# DDR3.net
KiCad netlist of a schematic drawn in Altium Designer
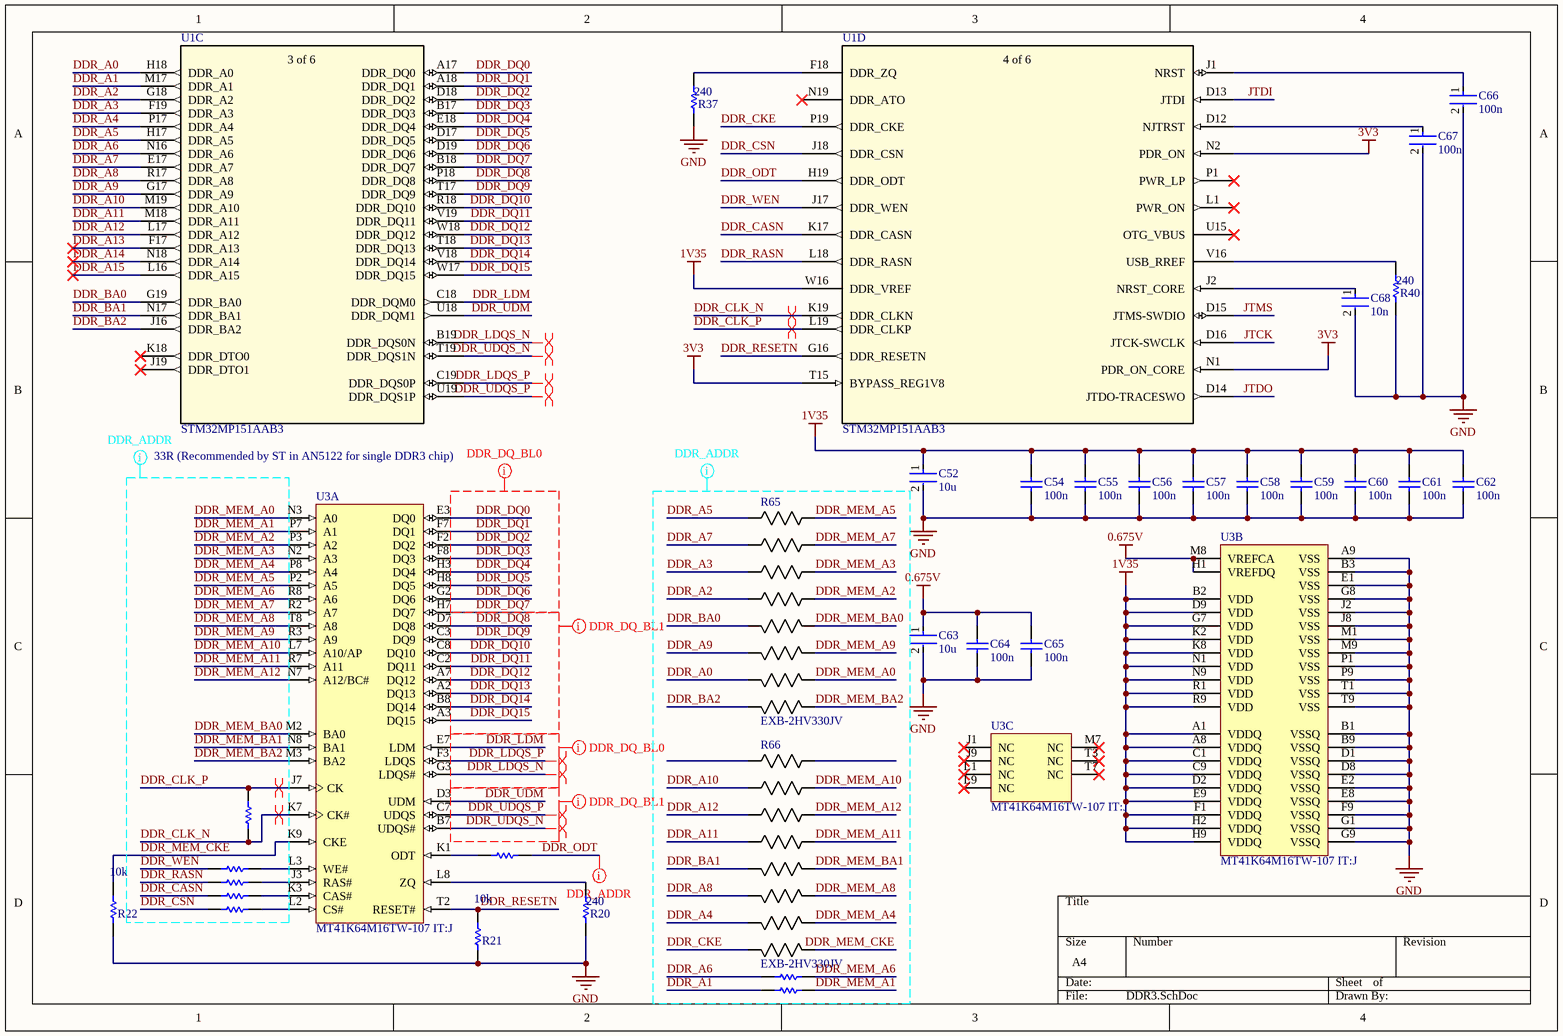
[diagram p0: DDR3.SchDoc]

(export (version "E")
  (design (tool "Eeschema 10.0.6"))
  (components
    (comp (ref "C52")
      (value "10u")
      (footprint "FP-CC0805-0_85-MFG")
      (description "CAP CER 0.1UF 50V X7R 0805")
      (fields (field (name "TOLERANCE") "0.1") (field (name "MANUFACTURER PART NUMBER") "CC0805KRX7R9BB104"))
      (libsource (lib "Altium Content Vault") (part "11868f565c42a9108669ba33697ecf6"))
    )
    (comp (ref "C54")
      (value "100n")
      (footprint "CAPC0603X33X15LL03T05")
      (fields
        (field (name "PART NUMBER") "02016D104KAT2A")
        (field (name "MANUFACTURER") "AVX Interconnect / Elco")
      )
      (libsource (lib "Altium Content Vault") (part "CAP"))
    )
    (comp (ref "C55")
      (value "100n")
      (footprint "CAPC0603X33X15LL03T05")
      (fields
        (field (name "PART NUMBER") "02016D104KAT2A")
        (field (name "MANUFACTURER") "AVX Interconnect / Elco")
      )
      (libsource (lib "Altium Content Vault") (part "CAP"))
    )
    (comp (ref "C56")
      (value "100n")
      (footprint "CAPC0603X33X15LL03T05")
      (fields
        (field (name "PART NUMBER") "02016D104KAT2A")
        (field (name "MANUFACTURER") "AVX Interconnect / Elco")
      )
      (libsource (lib "Altium Content Vault") (part "CAP"))
    )
    (comp (ref "C57")
      (value "100n")
      (footprint "CAPC0603X33X15LL03T05")
      (fields
        (field (name "PART NUMBER") "02016D104KAT2A")
        (field (name "MANUFACTURER") "AVX Interconnect / Elco")
      )
      (libsource (lib "Altium Content Vault") (part "CAP"))
    )
    (comp (ref "C58")
      (value "100n")
      (footprint "CAPC0603X33X15LL03T05")
      (fields
        (field (name "PART NUMBER") "02016D104KAT2A")
        (field (name "MANUFACTURER") "AVX Interconnect / Elco")
      )
      (libsource (lib "Altium Content Vault") (part "CAP"))
    )
    (comp (ref "C59")
      (value "100n")
      (footprint "CAPC0603X33X15LL03T05")
      (fields
        (field (name "PART NUMBER") "02016D104KAT2A")
        (field (name "MANUFACTURER") "AVX Interconnect / Elco")
      )
      (libsource (lib "Altium Content Vault") (part "CAP"))
    )
    (comp (ref "C60")
      (value "100n")
      (footprint "CAPC0603X33X15LL03T05")
      (fields
        (field (name "PART NUMBER") "02016D104KAT2A")
        (field (name "MANUFACTURER") "AVX Interconnect / Elco")
      )
      (libsource (lib "Altium Content Vault") (part "CAP"))
    )
    (comp (ref "C61")
      (value "100n")
      (footprint "CAPC0603X33X15LL03T05")
      (fields
        (field (name "PART NUMBER") "02016D104KAT2A")
        (field (name "MANUFACTURER") "AVX Interconnect / Elco")
      )
      (libsource (lib "Altium Content Vault") (part "CAP"))
    )
    (comp (ref "C62")
      (value "100n")
      (footprint "CAPC0603X33X15LL03T05")
      (fields
        (field (name "PART NUMBER") "02016D104KAT2A")
        (field (name "MANUFACTURER") "AVX Interconnect / Elco")
      )
      (libsource (lib "Altium Content Vault") (part "CAP"))
    )
    (comp (ref "C63")
      (value "10u")
      (footprint "FP-CC0805-0_85-MFG")
      (description "CAP CER 0.1UF 50V X7R 0805")
      (fields (field (name "TOLERANCE") "0.1") (field (name "MANUFACTURER PART NUMBER") "CC0805KRX7R9BB104"))
      (libsource (lib "Altium Content Vault") (part "11868f565c42a9108669ba33697ecf6"))
    )
    (comp (ref "C64")
      (value "100n")
      (footprint "CAPC0603X33X15LL03T05")
      (fields
        (field (name "PART NUMBER") "02016D104KAT2A")
        (field (name "MANUFACTURER") "AVX Interconnect / Elco")
      )
      (libsource (lib "Altium Content Vault") (part "CAP"))
    )
    (comp (ref "C65")
      (value "100n")
      (footprint "CAPC0603X33X15LL03T05")
      (fields
        (field (name "PART NUMBER") "02016D104KAT2A")
        (field (name "MANUFACTURER") "AVX Interconnect / Elco")
      )
      (libsource (lib "Altium Content Vault") (part "CAP"))
    )
    (comp (ref "C66")
      (value "100n")
      (footprint "FP-C0603C-CF-MFG")
      (description "CAP CER 0.1UF 50V X7R 0603")
      (fields (field (name "TOLERANCE") "0.1") (field (name "MANUFACTURER") "KEMET"))
      (libsource (lib "Altium Content Vault") (part "b4654b650e69147ec39a6b967a45e02"))
    )
    (comp (ref "C67")
      (value "100n")
      (footprint "FP-C0603C-CF-MFG")
      (description "CAP CER 0.1UF 50V X7R 0603")
      (fields (field (name "TOLERANCE") "0.1") (field (name "MANUFACTURER") "KEMET"))
      (libsource (lib "Altium Content Vault") (part "b4654b650e69147ec39a6b967a45e02"))
    )
    (comp (ref "C68")
      (value "10n")
      (footprint "FP-C0603C-CF-MFG")
      (description "CAP CER 0.1UF 50V X7R 0603")
      (fields (field (name "TOLERANCE") "0.1") (field (name "MANUFACTURER") "KEMET"))
      (libsource (lib "Altium Content Vault") (part "b4654b650e69147ec39a6b967a45e02"))
    )
    (comp (ref "R13")
      (value "CRCW0201100RFKED")
      (footprint "RESC0603X28X15ML05T05")
      (fields (field (name "MANUFACTURER") "Vishay"))
      (libsource (lib "Altium Content Vault") (part "RES"))
    )
    (comp (ref "R14")
      (value "CRCW0201100RFKED")
      (footprint "RESC0603X28X15ML05T05")
      (fields (field (name "MANUFACTURER") "Vishay"))
      (libsource (lib "Altium Content Vault") (part "RES"))
    )
    (comp (ref "R15")
      (value "CRCW0201100RFKED")
      (footprint "RESC0603X28X15ML05T05")
      (fields (field (name "MANUFACTURER") "Vishay"))
      (libsource (lib "Altium Content Vault") (part "RES"))
    )
    (comp (ref "R16")
      (value "CRCW0201100RFKED")
      (footprint "RESC0603X28X15ML05T05")
      (fields (field (name "MANUFACTURER") "Vishay"))
      (libsource (lib "Altium Content Vault") (part "RES"))
    )
    (comp (ref "R17")
      (value "CRCW0201100RFKED")
      (footprint "RESC0603X28X15ML05T05")
      (fields (field (name "MANUFACTURER") "Vishay"))
      (libsource (lib "Altium Content Vault") (part "RES"))
    )
    (comp (ref "R18")
      (value "CRCW0201100RFKED")
      (footprint "RESC0603X28X15ML05T05")
      (fields (field (name "MANUFACTURER") "Vishay"))
      (libsource (lib "Altium Content Vault") (part "RES"))
    )
    (comp (ref "R19")
      (value "CRCW0201100RFKED")
      (footprint "RESC0603X28X15ML05T05")
      (fields (field (name "MANUFACTURER") "Vishay"))
      (libsource (lib "Altium Content Vault") (part "RES"))
    )
    (comp (ref "R20")
      (value "240")
      (footprint "RESC1609X50X30NL8T20")
      (description "Chip Resistor, 10 KOhm, +/- 1%, 100 mW, -55 to 155 degC, 0603 (1608 Metric), RoHS, Tape and Reel")
      (fields (field (name "MANUFACTURER") "Vishay Semiconductor"))
      (libsource (lib "Altium Content Vault") (part "RES-2"))
    )
    (comp (ref "R21")
      (value "10k")
      (footprint "RESC0603X28X15ML05T05")
      (fields (field (name "PART NUMBER") "CRCW0201100RFKED") (field (name "MANUFACTURER") "Vishay"))
      (libsource (lib "Altium Content Vault") (part "RES"))
    )
    (comp (ref "R22")
      (value "10k")
      (footprint "RESC0603X28X15ML05T05")
      (fields (field (name "PART NUMBER") "CRCW0201100RFKED") (field (name "MANUFACTURER") "Vishay"))
      (libsource (lib "Altium Content Vault") (part "RES"))
    )
    (comp (ref "R29")
      (value "CRCW0201100RFKED")
      (footprint "RESC0603X28X15ML05T05")
      (fields (field (name "MANUFACTURER") "Vishay"))
      (libsource (lib "Altium Content Vault") (part "RES"))
    )
    (comp (ref "R37")
      (value "240")
      (footprint "RESC1609X50X30NL8T20")
      (description "Chip Resistor, 10 KOhm, +/- 1%, 100 mW, -55 to 155 degC, 0603 (1608 Metric), RoHS, Tape and Reel")
      (fields (field (name "MANUFACTURER") "Vishay Semiconductor"))
      (libsource (lib "Altium Content Vault") (part "RES-2"))
    )
    (comp (ref "R40")
      (value "240")
      (footprint "RESC1609X50X30NL8T20")
      (description "Chip Resistor, 10 KOhm, +/- 1%, 100 mW, -55 to 155 degC, 0603 (1608 Metric), RoHS, Tape and Reel")
      (fields (field (name "MANUFACTURER") "Vishay Semiconductor"))
      (libsource (lib "Altium Content Vault") (part "RES-2"))
    )
    (comp (ref "R65")
      (value "EXB-2HV330JV")
      (footprint "RES_EXB2HV")
      (description "No Description Available")
      (libsource (lib "Master") (part "EXB-2HV330JV"))
    )
    (comp (ref "R66")
      (value "EXB-2HV330JV")
      (footprint "RES_EXB2HV")
      (description "No Description Available")
      (libsource (lib "Master") (part "EXB-2HV330JV"))
    )
    (comp (ref "U1")
      (value "STM32MP151AAB3")
      (footprint "LFBGA354_16X16_STM")
      (description "No Description Available")
      (libsource (lib "Master") (part "STM32MP151AAB3"))
    )
    (comp (ref "U3")
      (value "MT41K64M16TW-107 IT:J")
      (footprint "MICT-TW-96")
      (description "1 Gb DDR3L 1866 SDRAM, 64 Mb x 16, 1.07 ns, 1.35 V, -40 to 95 degC, 96-Ball FBGA (TW), RoHS, Tray")
      (fields (field (name "MANUFACTURER") "Micron"))
      (libsource (lib "Altium Content Vault") (part "MICT-MT41K_1G-FBGA96"))
    )
  )
  (nets
    (net (code "1") (name "/DDR_A0") (class "Default")
      (node (ref "R65") (pin "7") (pinfunction "7_7") (pintype "passive"))
      (node (ref "U1") (pin "H18") (pinfunction "DDR_A0_H18") (pintype "output"))
    )
    (net (code "2") (name "/DDR_A1") (class "Default")
      (node (ref "R19") (pin "1") (pinfunction "1_1") (pintype "passive"))
      (node (ref "U1") (pin "M17") (pinfunction "DDR_A1_M17") (pintype "output"))
    )
    (net (code "3") (name "/DDR_A2") (class "Default")
      (node (ref "R65") (pin "4") (pinfunction "4_4") (pintype "passive"))
      (node (ref "U1") (pin "G18") (pinfunction "DDR_A2_G18") (pintype "output"))
    )
    (net (code "4") (name "/DDR_A3") (class "Default")
      (node (ref "R65") (pin "3") (pinfunction "3_3") (pintype "passive"))
      (node (ref "U1") (pin "F19") (pinfunction "DDR_A3_F19") (pintype "output"))
    )
    (net (code "5") (name "/DDR_A4") (class "Default")
      (node (ref "R66") (pin "7") (pinfunction "7_7") (pintype "passive"))
      (node (ref "U1") (pin "P17") (pinfunction "DDR_A4_P17") (pintype "output"))
    )
    (net (code "6") (name "/DDR_A5") (class "Default")
      (node (ref "R65") (pin "1") (pinfunction "1_1") (pintype "passive"))
      (node (ref "U1") (pin "H17") (pinfunction "DDR_A5_H17") (pintype "output"))
    )
    (net (code "7") (name "/DDR_A6") (class "Default")
      (node (ref "R18") (pin "1") (pinfunction "1_1") (pintype "passive"))
      (node (ref "U1") (pin "N16") (pinfunction "DDR_A6_N16") (pintype "output"))
    )
    (net (code "8") (name "/DDR_A7") (class "Default")
      (node (ref "R65") (pin "2") (pinfunction "2_2") (pintype "passive"))
      (node (ref "U1") (pin "E17") (pinfunction "DDR_A7_E17") (pintype "output"))
    )
    (net (code "9") (name "/DDR_A8") (class "Default")
      (node (ref "R66") (pin "6") (pinfunction "6_6") (pintype "passive"))
      (node (ref "U1") (pin "R17") (pinfunction "DDR_A8_R17") (pintype "output"))
    )
    (net (code "10") (name "/DDR_A9") (class "Default")
      (node (ref "R65") (pin "6") (pinfunction "6_6") (pintype "passive"))
      (node (ref "U1") (pin "G17") (pinfunction "DDR_A9_G17") (pintype "output"))
    )
    (net (code "11") (name "/DDR_A10") (class "Default")
      (node (ref "R66") (pin "2") (pinfunction "2_2") (pintype "passive"))
      (node (ref "U1") (pin "M19") (pinfunction "DDR_A10_M19") (pintype "output"))
    )
    (net (code "12") (name "/DDR_A11") (class "Default")
      (node (ref "R66") (pin "4") (pinfunction "4_4") (pintype "passive"))
      (node (ref "U1") (pin "M18") (pinfunction "DDR_A11_M18") (pintype "output"))
    )
    (net (code "13") (name "/DDR_A12") (class "Default")
      (node (ref "R66") (pin "3") (pinfunction "3_3") (pintype "passive"))
      (node (ref "U1") (pin "L17") (pinfunction "DDR_A12_L17") (pintype "output"))
    )
    (net (code "14") (name "/DDR_A13") (class "Default")
      (node (ref "U1") (pin "F17") (pinfunction "DDR_A13_F17") (pintype "output+no_connect"))
    )
    (net (code "15") (name "/DDR_A14") (class "Default")
      (node (ref "U1") (pin "N18") (pinfunction "DDR_A14_N18") (pintype "output+no_connect"))
    )
    (net (code "16") (name "/DDR_A15") (class "Default")
      (node (ref "U1") (pin "L16") (pinfunction "DDR_A15_L16") (pintype "output+no_connect"))
    )
    (net (code "17") (name "/DDR_BA0") (class "Default")
      (node (ref "R65") (pin "5") (pinfunction "5_5") (pintype "passive"))
      (node (ref "U1") (pin "G19") (pinfunction "DDR_BA0_G19") (pintype "output"))
    )
    (net (code "18") (name "/DDR_BA1") (class "Default")
      (node (ref "R66") (pin "5") (pinfunction "5_5") (pintype "passive"))
      (node (ref "U1") (pin "N17") (pinfunction "DDR_BA1_N17") (pintype "output"))
    )
    (net (code "19") (name "/DDR_BA2") (class "Default")
      (node (ref "R65") (pin "8") (pinfunction "8_8") (pintype "passive"))
      (node (ref "U1") (pin "J16") (pinfunction "DDR_BA2_J16") (pintype "output"))
    )
    (net (code "20") (name "/DDR_CASN") (class "Default")
      (node (ref "R16") (pin "1") (pinfunction "1_1") (pintype "passive"))
      (node (ref "U1") (pin "K17") (pinfunction "DDR_CASN_K17") (pintype "output"))
    )
    (net (code "21") (name "/DDR_CKE") (class "Default")
      (node (ref "R66") (pin "8") (pinfunction "8_8") (pintype "passive"))
      (node (ref "U1") (pin "P19") (pinfunction "DDR_CKE_P19") (pintype "output"))
    )
    (net (code "22") (name "/DDR_CLK_N") (class "Default")
      (node (ref "R29") (pin "1") (pinfunction "1_1") (pintype "passive"))
      (node (ref "U1") (pin "K19") (pinfunction "DDR_CLKN_K19") (pintype "output"))
      (node (ref "U3") (pin "K7") (pinfunction "CK#_K7") (pintype "input"))
    )
    (net (code "23") (name "/DDR_CLK_P") (class "Default")
      (node (ref "R29") (pin "2") (pinfunction "2_2") (pintype "passive"))
      (node (ref "U1") (pin "L19") (pinfunction "DDR_CLKP_L19") (pintype "output"))
      (node (ref "U3") (pin "J7") (pinfunction "CK_J7") (pintype "input"))
    )
    (net (code "24") (name "/DDR_CSN") (class "Default")
      (node (ref "R17") (pin "1") (pinfunction "1_1") (pintype "passive"))
      (node (ref "U1") (pin "J18") (pinfunction "DDR_CSN_J18") (pintype "output"))
    )
    (net (code "25") (name "/DDR_DQ0") (class "Default")
      (node (ref "U1") (pin "A17") (pinfunction "DDR_DQ0_A17") (pintype "bidirectional"))
      (node (ref "U3") (pin "E3") (pinfunction "DQ0_E3") (pintype "bidirectional"))
    )
    (net (code "26") (name "/DDR_DQ1") (class "Default")
      (node (ref "U1") (pin "A18") (pinfunction "DDR_DQ1_A18") (pintype "bidirectional"))
      (node (ref "U3") (pin "F7") (pinfunction "DQ1_F7") (pintype "bidirectional"))
    )
    (net (code "27") (name "/DDR_DQ2") (class "Default")
      (node (ref "U1") (pin "D18") (pinfunction "DDR_DQ2_D18") (pintype "bidirectional"))
      (node (ref "U3") (pin "F2") (pinfunction "DQ2_F2") (pintype "bidirectional"))
    )
    (net (code "28") (name "/DDR_DQ3") (class "Default")
      (node (ref "U1") (pin "B17") (pinfunction "DDR_DQ3_B17") (pintype "bidirectional"))
      (node (ref "U3") (pin "F8") (pinfunction "DQ3_F8") (pintype "bidirectional"))
    )
    (net (code "29") (name "/DDR_DQ4") (class "Default")
      (node (ref "U1") (pin "E18") (pinfunction "DDR_DQ4_E18") (pintype "bidirectional"))
      (node (ref "U3") (pin "H3") (pinfunction "DQ4_H3") (pintype "bidirectional"))
    )
    (net (code "30") (name "/DDR_DQ5") (class "Default")
      (node (ref "U1") (pin "D17") (pinfunction "DDR_DQ5_D17") (pintype "bidirectional"))
      (node (ref "U3") (pin "H8") (pinfunction "DQ5_H8") (pintype "bidirectional"))
    )
    (net (code "31") (name "/DDR_DQ6") (class "Default")
      (node (ref "U1") (pin "D19") (pinfunction "DDR_DQ6_D19") (pintype "bidirectional"))
      (node (ref "U3") (pin "G2") (pinfunction "DQ6_G2") (pintype "bidirectional"))
    )
    (net (code "32") (name "/DDR_DQ7") (class "Default")
      (node (ref "U1") (pin "B18") (pinfunction "DDR_DQ7_B18") (pintype "bidirectional"))
      (node (ref "U3") (pin "H7") (pinfunction "DQ7_H7") (pintype "bidirectional"))
    )
    (net (code "33") (name "/DDR_DQ8") (class "Default")
      (node (ref "U1") (pin "P18") (pinfunction "DDR_DQ8_P18") (pintype "bidirectional"))
      (node (ref "U3") (pin "D7") (pinfunction "DQ8_D7") (pintype "bidirectional"))
    )
    (net (code "34") (name "/DDR_DQ9") (class "Default")
      (node (ref "U1") (pin "T17") (pinfunction "DDR_DQ9_T17") (pintype "bidirectional"))
      (node (ref "U3") (pin "C3") (pinfunction "DQ9_C3") (pintype "bidirectional"))
    )
    (net (code "35") (name "/DDR_DQ10") (class "Default")
      (node (ref "U1") (pin "R18") (pinfunction "DDR_DQ10_R18") (pintype "bidirectional"))
      (node (ref "U3") (pin "C8") (pinfunction "DQ10_C8") (pintype "bidirectional"))
    )
    (net (code "36") (name "/DDR_DQ11") (class "Default")
      (node (ref "U1") (pin "V19") (pinfunction "DDR_DQ11_V19") (pintype "bidirectional"))
      (node (ref "U3") (pin "C2") (pinfunction "DQ11_C2") (pintype "bidirectional"))
    )
    (net (code "37") (name "/DDR_DQ12") (class "Default")
      (node (ref "U1") (pin "W18") (pinfunction "DDR_DQ12_W18") (pintype "bidirectional"))
      (node (ref "U3") (pin "A7") (pinfunction "DQ12_A7") (pintype "bidirectional"))
    )
    (net (code "38") (name "/DDR_DQ13") (class "Default")
      (node (ref "U1") (pin "T18") (pinfunction "DDR_DQ13_T18") (pintype "bidirectional"))
      (node (ref "U3") (pin "A2") (pinfunction "DQ13_A2") (pintype "bidirectional"))
    )
    (net (code "39") (name "/DDR_DQ14") (class "Default")
      (node (ref "U1") (pin "V18") (pinfunction "DDR_DQ14_V18") (pintype "bidirectional"))
      (node (ref "U3") (pin "B8") (pinfunction "DQ14_B8") (pintype "bidirectional"))
    )
    (net (code "40") (name "/DDR_DQ15") (class "Default")
      (node (ref "U1") (pin "W17") (pinfunction "DDR_DQ15_W17") (pintype "bidirectional"))
      (node (ref "U3") (pin "A3") (pinfunction "DQ15_A3") (pintype "bidirectional"))
    )
    (net (code "41") (name "/DDR_LDM") (class "Default")
      (node (ref "U1") (pin "C18") (pinfunction "DDR_DQM0_C18") (pintype "output"))
      (node (ref "U3") (pin "E7") (pinfunction "LDM_E7") (pintype "input"))
    )
    (net (code "42") (name "/DDR_LDQS_N") (class "Default")
      (node (ref "U1") (pin "B19") (pinfunction "DDR_DQS0N_B19") (pintype "bidirectional"))
      (node (ref "U3") (pin "G3") (pinfunction "LDQS#_G3") (pintype "bidirectional"))
    )
    (net (code "43") (name "/DDR_LDQS_P") (class "Default")
      (node (ref "U1") (pin "C19") (pinfunction "DDR_DQS0P_C19") (pintype "bidirectional"))
      (node (ref "U3") (pin "F3") (pinfunction "LDQS_F3") (pintype "bidirectional"))
    )
    (net (code "44") (name "/DDR_MEM_A0") (class "Default")
      (node (ref "R65") (pin "10") (pinfunction "10_10") (pintype "passive"))
      (node (ref "U3") (pin "N3") (pinfunction "A0_N3") (pintype "input"))
    )
    (net (code "45") (name "/DDR_MEM_A1") (class "Default")
      (node (ref "R19") (pin "2") (pinfunction "2_2") (pintype "passive"))
      (node (ref "U3") (pin "P7") (pinfunction "A1_P7") (pintype "input"))
    )
    (net (code "46") (name "/DDR_MEM_A2") (class "Default")
      (node (ref "R65") (pin "13") (pinfunction "13_13") (pintype "passive"))
      (node (ref "U3") (pin "P3") (pinfunction "A2_P3") (pintype "input"))
    )
    (net (code "47") (name "/DDR_MEM_A3") (class "Default")
      (node (ref "R65") (pin "14") (pinfunction "14_14") (pintype "passive"))
      (node (ref "U3") (pin "N2") (pinfunction "A3_N2") (pintype "input"))
    )
    (net (code "48") (name "/DDR_MEM_A4") (class "Default")
      (node (ref "R66") (pin "10") (pinfunction "10_10") (pintype "passive"))
      (node (ref "U3") (pin "P8") (pinfunction "A4_P8") (pintype "input"))
    )
    (net (code "49") (name "/DDR_MEM_A5") (class "Default")
      (node (ref "R65") (pin "16") (pinfunction "16_16") (pintype "passive"))
      (node (ref "U3") (pin "P2") (pinfunction "A5_P2") (pintype "input"))
    )
    (net (code "50") (name "/DDR_MEM_A6") (class "Default")
      (node (ref "R18") (pin "2") (pinfunction "2_2") (pintype "passive"))
      (node (ref "U3") (pin "R8") (pinfunction "A6_R8") (pintype "input"))
    )
    (net (code "51") (name "/DDR_MEM_A7") (class "Default")
      (node (ref "R65") (pin "15") (pinfunction "15_15") (pintype "passive"))
      (node (ref "U3") (pin "R2") (pinfunction "A7_R2") (pintype "input"))
    )
    (net (code "52") (name "/DDR_MEM_A8") (class "Default")
      (node (ref "R66") (pin "11") (pinfunction "11_11") (pintype "passive"))
      (node (ref "U3") (pin "T8") (pinfunction "A8_T8") (pintype "input"))
    )
    (net (code "53") (name "/DDR_MEM_A9") (class "Default")
      (node (ref "R65") (pin "11") (pinfunction "11_11") (pintype "passive"))
      (node (ref "U3") (pin "R3") (pinfunction "A9_R3") (pintype "input"))
    )
    (net (code "54") (name "/DDR_MEM_A10") (class "Default")
      (node (ref "R66") (pin "15") (pinfunction "15_15") (pintype "passive"))
      (node (ref "U3") (pin "L7") (pinfunction "A10/AP_L7") (pintype "input"))
    )
    (net (code "55") (name "/DDR_MEM_A11") (class "Default")
      (node (ref "R66") (pin "13") (pinfunction "13_13") (pintype "passive"))
      (node (ref "U3") (pin "R7") (pinfunction "A11_R7") (pintype "input"))
    )
    (net (code "56") (name "/DDR_MEM_A12") (class "Default")
      (node (ref "R66") (pin "14") (pinfunction "14_14") (pintype "passive"))
      (node (ref "U3") (pin "N7") (pinfunction "A12/BC#_N7") (pintype "input"))
    )
    (net (code "57") (name "/DDR_MEM_BA0") (class "Default")
      (node (ref "R65") (pin "12") (pinfunction "12_12") (pintype "passive"))
      (node (ref "U3") (pin "M2") (pinfunction "BA0_M2") (pintype "input"))
    )
    (net (code "58") (name "/DDR_MEM_BA1") (class "Default")
      (node (ref "R66") (pin "12") (pinfunction "12_12") (pintype "passive"))
      (node (ref "U3") (pin "N8") (pinfunction "BA1_N8") (pintype "input"))
    )
    (net (code "59") (name "/DDR_MEM_BA2") (class "Default")
      (node (ref "R65") (pin "9") (pinfunction "9_9") (pintype "passive"))
      (node (ref "U3") (pin "M3") (pinfunction "BA2_M3") (pintype "input"))
    )
    (net (code "60") (name "/DDR_MEM_CKE") (class "Default")
      (node (ref "R22") (pin "2") (pinfunction "2_2") (pintype "passive"))
      (node (ref "R66") (pin "9") (pinfunction "9_9") (pintype "passive"))
      (node (ref "U3") (pin "K9") (pinfunction "CKE_K9") (pintype "input"))
    )
    (net (code "61") (name "/DDR_ODT") (class "Default")
      (node (ref "R13") (pin "2") (pinfunction "2_2") (pintype "passive"))
      (node (ref "U1") (pin "H19") (pinfunction "DDR_ODT_H19") (pintype "output"))
    )
    (net (code "62") (name "/DDR_RASN") (class "Default")
      (node (ref "R15") (pin "1") (pinfunction "1_1") (pintype "passive"))
      (node (ref "U1") (pin "L18") (pinfunction "DDR_RASN_L18") (pintype "output"))
    )
    (net (code "63") (name "/DDR_RESETN") (class "Default")
      (node (ref "R21") (pin "2") (pinfunction "2_2") (pintype "passive"))
      (node (ref "U1") (pin "G16") (pinfunction "DDR_RESETN_G16") (pintype "output"))
      (node (ref "U3") (pin "T2") (pinfunction "RESET#_T2") (pintype "input"))
    )
    (net (code "64") (name "/DDR_UDM") (class "Default")
      (node (ref "U1") (pin "U18") (pinfunction "DDR_DQM1_U18") (pintype "output"))
      (node (ref "U3") (pin "D3") (pinfunction "UDM_D3") (pintype "input"))
    )
    (net (code "65") (name "/DDR_UDQS_N") (class "Default")
      (node (ref "U1") (pin "T19") (pinfunction "DDR_DQS1N_T19") (pintype "bidirectional"))
      (node (ref "U3") (pin "B7") (pinfunction "UDQS#_B7") (pintype "bidirectional"))
    )
    (net (code "66") (name "/DDR_UDQS_P") (class "Default")
      (node (ref "U1") (pin "U19") (pinfunction "DDR_DQS1P_U19") (pintype "bidirectional"))
      (node (ref "U3") (pin "C7") (pinfunction "UDQS_C7") (pintype "bidirectional"))
    )
    (net (code "67") (name "/DDR_WEN") (class "Default")
      (node (ref "R14") (pin "1") (pinfunction "1_1") (pintype "passive"))
      (node (ref "U1") (pin "J17") (pinfunction "DDR_WEN_J17") (pintype "output"))
    )
    (net (code "68") (name "/JTCK") (class "Default")
      (node (ref "U1") (pin "D16") (pinfunction "JTCK-SWCLK_D16") (pintype "input"))
    )
    (net (code "69") (name "/JTDI") (class "Default")
      (node (ref "U1") (pin "D13") (pinfunction "JTDI_D13") (pintype "input"))
    )
    (net (code "70") (name "/JTDO") (class "Default")
      (node (ref "U1") (pin "D14") (pinfunction "JTDO-TRACESWO_D14") (pintype "output"))
    )
    (net (code "71") (name "/JTMS") (class "Default")
      (node (ref "U1") (pin "D15") (pinfunction "JTMS-SWDIO_D15") (pintype "bidirectional"))
    )
    (net (code "72") (name "0.675V") (class "Default")
      (node (ref "C63") (pin "1") (pinfunction "1_1") (pintype "passive"))
      (node (ref "C64") (pin "2") (pinfunction "2_2") (pintype "passive"))
      (node (ref "C65") (pin "2") (pinfunction "2_2") (pintype "passive"))
      (node (ref "U3") (pin "H1") (pinfunction "VREFDQ_H1") (pintype "power_in"))
      (node (ref "U3") (pin "M8") (pinfunction "VREFCA_M8") (pintype "power_in"))
    )
    (net (code "73") (name "1V35") (class "Default")
      (node (ref "C52") (pin "1") (pinfunction "1_1") (pintype "passive"))
      (node (ref "C54") (pin "2") (pinfunction "2_2") (pintype "passive"))
      (node (ref "C55") (pin "2") (pinfunction "2_2") (pintype "passive"))
      (node (ref "C56") (pin "2") (pinfunction "2_2") (pintype "passive"))
      (node (ref "C57") (pin "2") (pinfunction "2_2") (pintype "passive"))
      (node (ref "C58") (pin "2") (pinfunction "2_2") (pintype "passive"))
      (node (ref "C59") (pin "2") (pinfunction "2_2") (pintype "passive"))
      (node (ref "C60") (pin "2") (pinfunction "2_2") (pintype "passive"))
      (node (ref "C61") (pin "2") (pinfunction "2_2") (pintype "passive"))
      (node (ref "C62") (pin "2") (pinfunction "2_2") (pintype "passive"))
      (node (ref "U1") (pin "W16") (pinfunction "DDR_VREF_W16") (pintype "passive"))
      (node (ref "U3") (pin "A1") (pinfunction "VDDQ_A1") (pintype "power_in"))
      (node (ref "U3") (pin "A8") (pinfunction "VDDQ_A8") (pintype "power_in"))
      (node (ref "U3") (pin "B2") (pinfunction "VDD_B2") (pintype "power_in"))
      (node (ref "U3") (pin "C1") (pinfunction "VDDQ_C1") (pintype "power_in"))
      (node (ref "U3") (pin "C9") (pinfunction "VDDQ_C9") (pintype "power_in"))
      (node (ref "U3") (pin "D2") (pinfunction "VDDQ_D2") (pintype "power_in"))
      (node (ref "U3") (pin "D9") (pinfunction "VDD_D9") (pintype "power_in"))
      (node (ref "U3") (pin "E9") (pinfunction "VDDQ_E9") (pintype "power_in"))
      (node (ref "U3") (pin "F1") (pinfunction "VDDQ_F1") (pintype "power_in"))
      (node (ref "U3") (pin "G7") (pinfunction "VDD_G7") (pintype "power_in"))
      (node (ref "U3") (pin "H2") (pinfunction "VDDQ_H2") (pintype "power_in"))
      (node (ref "U3") (pin "H9") (pinfunction "VDDQ_H9") (pintype "power_in"))
      (node (ref "U3") (pin "K2") (pinfunction "VDD_K2") (pintype "power_in"))
      (node (ref "U3") (pin "K8") (pinfunction "VDD_K8") (pintype "power_in"))
      (node (ref "U3") (pin "N1") (pinfunction "VDD_N1") (pintype "power_in"))
      (node (ref "U3") (pin "N9") (pinfunction "VDD_N9") (pintype "power_in"))
      (node (ref "U3") (pin "R1") (pinfunction "VDD_R1") (pintype "power_in"))
      (node (ref "U3") (pin "R9") (pinfunction "VDD_R9") (pintype "power_in"))
    )
    (net (code "74") (name "3V3") (class "Default")
      (node (ref "U1") (pin "N1") (pinfunction "PDR_ON_CORE_N1") (pintype "input"))
      (node (ref "U1") (pin "N2") (pinfunction "PDR_ON_N2") (pintype "input"))
      (node (ref "U1") (pin "T15") (pinfunction "BYPASS_REG1V8_T15") (pintype "input"))
    )
    (net (code "75") (name "GND") (class "Default")
      (node (ref "C52") (pin "2") (pinfunction "2_2") (pintype "passive"))
      (node (ref "C54") (pin "1") (pinfunction "1_1") (pintype "passive"))
      (node (ref "C55") (pin "1") (pinfunction "1_1") (pintype "passive"))
      (node (ref "C56") (pin "1") (pinfunction "1_1") (pintype "passive"))
      (node (ref "C57") (pin "1") (pinfunction "1_1") (pintype "passive"))
      (node (ref "C58") (pin "1") (pinfunction "1_1") (pintype "passive"))
      (node (ref "C59") (pin "1") (pinfunction "1_1") (pintype "passive"))
      (node (ref "C60") (pin "1") (pinfunction "1_1") (pintype "passive"))
      (node (ref "C61") (pin "1") (pinfunction "1_1") (pintype "passive"))
      (node (ref "C62") (pin "1") (pinfunction "1_1") (pintype "passive"))
      (node (ref "C63") (pin "2") (pinfunction "2_2") (pintype "passive"))
      (node (ref "C64") (pin "1") (pinfunction "1_1") (pintype "passive"))
      (node (ref "C65") (pin "1") (pinfunction "1_1") (pintype "passive"))
      (node (ref "C66") (pin "2") (pinfunction "2_2") (pintype "passive"))
      (node (ref "C67") (pin "2") (pinfunction "2_2") (pintype "passive"))
      (node (ref "C68") (pin "2") (pinfunction "2_2") (pintype "passive"))
      (node (ref "R20") (pin "1") (pinfunction "1_1") (pintype "passive"))
      (node (ref "R21") (pin "1") (pinfunction "1_1") (pintype "passive"))
      (node (ref "R22") (pin "1") (pinfunction "1_1") (pintype "passive"))
      (node (ref "R37") (pin "1") (pinfunction "1_1") (pintype "passive"))
      (node (ref "R40") (pin "1") (pinfunction "1_1") (pintype "passive"))
      (node (ref "U3") (pin "A9") (pinfunction "VSS_A9") (pintype "power_in"))
      (node (ref "U3") (pin "B1") (pinfunction "VSSQ_B1") (pintype "power_in"))
      (node (ref "U3") (pin "B3") (pinfunction "VSS_B3") (pintype "power_in"))
      (node (ref "U3") (pin "B9") (pinfunction "VSSQ_B9") (pintype "power_in"))
      (node (ref "U3") (pin "D1") (pinfunction "VSSQ_D1") (pintype "power_in"))
      (node (ref "U3") (pin "D8") (pinfunction "VSSQ_D8") (pintype "power_in"))
      (node (ref "U3") (pin "E1") (pinfunction "VSS_E1") (pintype "power_in"))
      (node (ref "U3") (pin "E2") (pinfunction "VSSQ_E2") (pintype "power_in"))
      (node (ref "U3") (pin "E8") (pinfunction "VSSQ_E8") (pintype "power_in"))
      (node (ref "U3") (pin "F9") (pinfunction "VSSQ_F9") (pintype "power_in"))
      (node (ref "U3") (pin "G1") (pinfunction "VSSQ_G1") (pintype "power_in"))
      (node (ref "U3") (pin "G8") (pinfunction "VSS_G8") (pintype "power_in"))
      (node (ref "U3") (pin "G9") (pinfunction "VSSQ_G9") (pintype "power_in"))
      (node (ref "U3") (pin "J2") (pinfunction "VSS_J2") (pintype "power_in"))
      (node (ref "U3") (pin "J8") (pinfunction "VSS_J8") (pintype "power_in"))
      (node (ref "U3") (pin "M1") (pinfunction "VSS_M1") (pintype "power_in"))
      (node (ref "U3") (pin "M9") (pinfunction "VSS_M9") (pintype "power_in"))
      (node (ref "U3") (pin "P1") (pinfunction "VSS_P1") (pintype "power_in"))
      (node (ref "U3") (pin "P9") (pinfunction "VSS_P9") (pintype "power_in"))
      (node (ref "U3") (pin "T1") (pinfunction "VSS_T1") (pintype "power_in"))
      (node (ref "U3") (pin "T9") (pinfunction "VSS_T9") (pintype "power_in"))
    )
    (net (code "76") (name "Net-(U1D-DDR_ZQ)") (class "Default")
      (node (ref "R37") (pin "2") (pinfunction "2_2") (pintype "passive"))
      (node (ref "U1") (pin "F18") (pinfunction "DDR_ZQ_F18") (pintype "passive"))
    )
    (net (code "77") (name "Net-(U1D-NJTRST)") (class "Default")
      (node (ref "C67") (pin "1") (pinfunction "1_1") (pintype "passive"))
      (node (ref "U1") (pin "D12") (pinfunction "NJTRST_D12") (pintype "input"))
    )
    (net (code "78") (name "Net-(U1D-NRST)") (class "Default")
      (node (ref "C66") (pin "1") (pinfunction "1_1") (pintype "passive"))
      (node (ref "U1") (pin "J1") (pinfunction "NRST_J1") (pintype "bidirectional"))
    )
    (net (code "79") (name "Net-(U1D-NRST_CORE)") (class "Default")
      (node (ref "C68") (pin "1") (pinfunction "1_1") (pintype "passive"))
      (node (ref "U1") (pin "J2") (pinfunction "NRST_CORE_J2") (pintype "input"))
    )
    (net (code "80") (name "Net-(U1D-USB_RREF)") (class "Default")
      (node (ref "R40") (pin "2") (pinfunction "2_2") (pintype "passive"))
      (node (ref "U1") (pin "V16") (pinfunction "USB_RREF_V16") (pintype "passive"))
    )
    (net (code "81") (name "Net-(U3A-CAS#)") (class "Default")
      (node (ref "R16") (pin "2") (pinfunction "2_2") (pintype "passive"))
      (node (ref "U3") (pin "K3") (pinfunction "CAS#_K3") (pintype "input"))
    )
    (net (code "82") (name "Net-(U3A-CS#)") (class "Default")
      (node (ref "R17") (pin "2") (pinfunction "2_2") (pintype "passive"))
      (node (ref "U3") (pin "L2") (pinfunction "CS#_L2") (pintype "input"))
    )
    (net (code "83") (name "Net-(U3A-ODT)") (class "Default")
      (node (ref "R13") (pin "1") (pinfunction "1_1") (pintype "passive"))
      (node (ref "U3") (pin "K1") (pinfunction "ODT_K1") (pintype "input"))
    )
    (net (code "84") (name "Net-(U3A-RAS#)") (class "Default")
      (node (ref "R15") (pin "2") (pinfunction "2_2") (pintype "passive"))
      (node (ref "U3") (pin "J3") (pinfunction "RAS#_J3") (pintype "input"))
    )
    (net (code "85") (name "Net-(U3A-WE#)") (class "Default")
      (node (ref "R14") (pin "2") (pinfunction "2_2") (pintype "passive"))
      (node (ref "U3") (pin "L3") (pinfunction "WE#_L3") (pintype "input"))
    )
    (net (code "86") (name "Net-(U3A-ZQ)") (class "Default")
      (node (ref "R20") (pin "2") (pinfunction "2_2") (pintype "passive"))
      (node (ref "U3") (pin "L8") (pinfunction "ZQ_L8") (pintype "input"))
    )
    (net (code "87") (name "unconnected-(R66-Pad1)") (class "Default")
      (node (ref "R66") (pin "1") (pinfunction "1_1") (pintype "passive"))
    )
    (net (code "88") (name "unconnected-(R66-Pad16)") (class "Default")
      (node (ref "R66") (pin "16") (pinfunction "16_16") (pintype "passive"))
    )
    (net (code "89") (name "unconnected-(U1C-DDR_DTO0-PadK18)") (class "Default")
      (node (ref "U1") (pin "K18") (pinfunction "DDR_DTO0_K18") (pintype "output+no_connect"))
    )
    (net (code "90") (name "unconnected-(U1C-DDR_DTO1-PadJ19)") (class "Default")
      (node (ref "U1") (pin "J19") (pinfunction "DDR_DTO1_J19") (pintype "output+no_connect"))
    )
    (net (code "91") (name "unconnected-(U1D-DDR_ATO-PadN19)") (class "Default")
      (node (ref "U1") (pin "N19") (pinfunction "DDR_ATO_N19") (pintype "passive+no_connect"))
    )
    (net (code "92") (name "unconnected-(U1D-OTG_VBUS-PadU15)") (class "Default")
      (node (ref "U1") (pin "U15") (pinfunction "OTG_VBUS_U15") (pintype "passive+no_connect"))
    )
    (net (code "93") (name "unconnected-(U1D-PWR_LP-PadP1)") (class "Default")
      (node (ref "U1") (pin "P1") (pinfunction "PWR_LP_P1") (pintype "output+no_connect"))
    )
    (net (code "94") (name "unconnected-(U1D-PWR_ON-PadL1)") (class "Default")
      (node (ref "U1") (pin "L1") (pinfunction "PWR_ON_L1") (pintype "output+no_connect"))
    )
    (net (code "95") (name "unconnected-(U3C-NC-PadJ1)") (class "Default")
      (node (ref "U3") (pin "J1") (pinfunction "NC_J1") (pintype "passive+no_connect"))
    )
    (net (code "96") (name "unconnected-(U3C-NC-PadJ9)") (class "Default")
      (node (ref "U3") (pin "J9") (pinfunction "NC_J9") (pintype "passive+no_connect"))
    )
    (net (code "97") (name "unconnected-(U3C-NC-PadL1)") (class "Default")
      (node (ref "U3") (pin "L1") (pinfunction "NC_L1") (pintype "passive+no_connect"))
    )
    (net (code "98") (name "unconnected-(U3C-NC-PadL9)") (class "Default")
      (node (ref "U3") (pin "L9") (pinfunction "NC_L9") (pintype "passive+no_connect"))
    )
    (net (code "99") (name "unconnected-(U3C-NC-PadM7)") (class "Default")
      (node (ref "U3") (pin "M7") (pinfunction "NC_M7") (pintype "passive+no_connect"))
    )
    (net (code "100") (name "unconnected-(U3C-NC-PadT3)") (class "Default")
      (node (ref "U3") (pin "T3") (pinfunction "NC_T3") (pintype "passive+no_connect"))
    )
    (net (code "101") (name "unconnected-(U3C-NC-PadT7)") (class "Default")
      (node (ref "U3") (pin "T7") (pinfunction "NC_T7") (pintype "passive+no_connect"))
    )
  )
)
